# PAYL0012_GMSK_Prototyping_Board_no_proto.net
KiCad netlist of a schematic drawn in Altium Designer
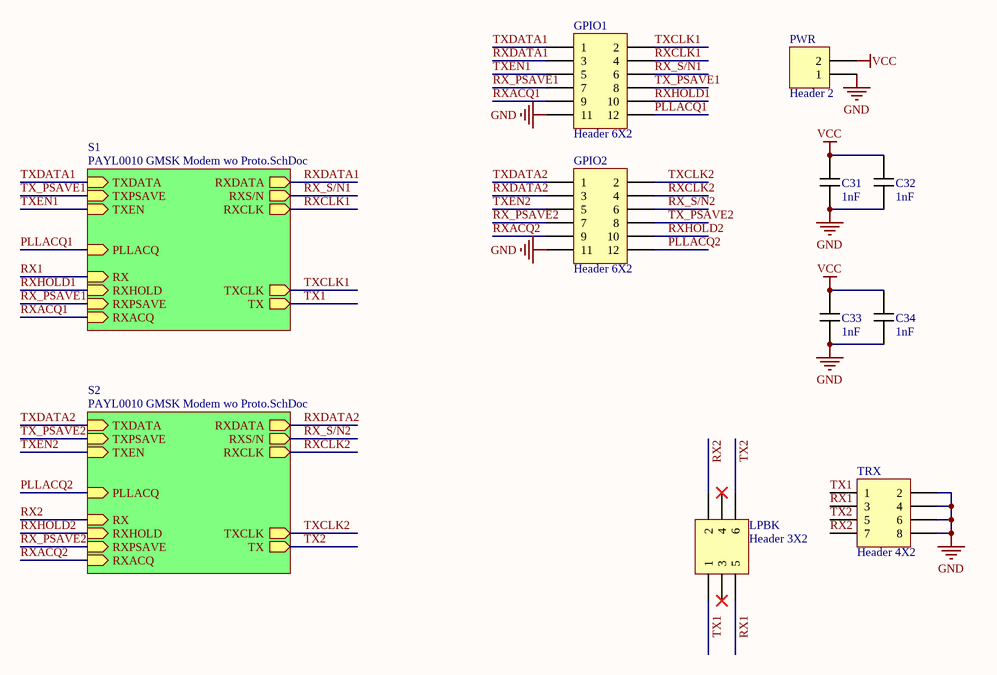
[diagram p0: PAYL0012 GMSK Prototyping Board no proto.SchDoc]

(export (version "E")
  (design (tool "Eeschema 10.0.6"))
  (components
    (comp (ref "C31")
      (value "1nF")
      (footprint "0805 Cap")
      (description "0805 MLCC - X7R, 10%")
      (fields (field (name "Comment") "0805 Cap"))
      (libsource (lib "GMSK Prototyping Board") (part "0805 MLCC - X7R, 10%"))
    )
    (comp (ref "C32")
      (value "1nF")
      (footprint "0805 Cap")
      (description "0805 MLCC - X7R, 10%")
      (fields (field (name "Comment") "0805 Cap"))
      (libsource (lib "GMSK Prototyping Board") (part "0805 MLCC - X7R, 10%"))
    )
    (comp (ref "C33")
      (value "1nF")
      (footprint "0805 Cap")
      (description "0805 MLCC - X7R, 10%")
      (fields (field (name "Comment") "0805 Cap"))
      (libsource (lib "GMSK Prototyping Board") (part "0805 MLCC - X7R, 10%"))
    )
    (comp (ref "C34")
      (value "1nF")
      (footprint "0805 Cap")
      (description "0805 MLCC - X7R, 10%")
      (fields (field (name "Comment") "0805 Cap"))
      (libsource (lib "GMSK Prototyping Board") (part "0805 MLCC - X7R, 10%"))
    )
    (comp (ref "GPIO1")
      (value "Header 6X2")
      (footprint "HDR2X6")
      (description "Header, 6-Pin, Dual row")
      (fields (field (name "PUBLISHER") "Altium Limited"))
      (libsource (lib "GMSK Prototyping Board") (part "Header 6X2"))
    )
    (comp (ref "GPIO2")
      (value "Header 6X2")
      (footprint "HDR2X6")
      (description "Header, 6-Pin, Dual row")
      (fields (field (name "PUBLISHER") "Altium Limited"))
      (libsource (lib "GMSK Prototyping Board") (part "Header 6X2"))
    )
    (comp (ref "LPBK")
      (value "Header 3X2")
      (footprint "HDR2X3")
      (description "Header, 3-Pin, Dual row")
      (fields (field (name "PUBLISHER") "Altium Limited"))
      (libsource (lib "GMSK Prototyping Board") (part "Header 3X2"))
    )
    (comp (ref "PWR")
      (value "Header 2")
      (footprint "HDR1X2")
      (description "Header, 2-Pin")
      (fields (field (name "PUBLISHER") "Altium Limited"))
      (libsource (lib "GMSK Prototyping Board") (part "Header 2"))
    )
    (comp (ref "TRX")
      (value "Header 4X2")
      (footprint "HDR2X4")
      (description "Header, 4-Pin, Dual row")
      (fields (field (name "PUBLISHER") "Altium Limited"))
      (libsource (lib "GMSK Prototyping Board") (part "Header 4X2"))
    )
  )
  (nets
    (net (code "1") (name "/PLLACQ1") (class "Default")
      (node (ref "GPIO1") (pin "12") (pinfunction "12_12") (pintype "passive"))
    )
    (net (code "2") (name "/PLLACQ2") (class "Default")
      (node (ref "GPIO2") (pin "12") (pinfunction "12_12") (pintype "passive"))
    )
    (net (code "3") (name "/RX1") (class "Default")
      (node (ref "LPBK") (pin "5") (pinfunction "5_5") (pintype "passive"))
      (node (ref "TRX") (pin "3") (pinfunction "3_3") (pintype "passive"))
    )
    (net (code "4") (name "/RX2") (class "Default")
      (node (ref "LPBK") (pin "2") (pinfunction "2_2") (pintype "passive"))
      (node (ref "TRX") (pin "7") (pinfunction "7_7") (pintype "passive"))
    )
    (net (code "5") (name "/RXACQ1") (class "Default")
      (node (ref "GPIO1") (pin "9") (pinfunction "9_9") (pintype "passive"))
    )
    (net (code "6") (name "/RXACQ2") (class "Default")
      (node (ref "GPIO2") (pin "9") (pinfunction "9_9") (pintype "passive"))
    )
    (net (code "7") (name "/RXCLK1") (class "Default")
      (node (ref "GPIO1") (pin "4") (pinfunction "4_4") (pintype "passive"))
    )
    (net (code "8") (name "/RXCLK2") (class "Default")
      (node (ref "GPIO2") (pin "4") (pinfunction "4_4") (pintype "passive"))
    )
    (net (code "9") (name "/RXDATA1") (class "Default")
      (node (ref "GPIO1") (pin "3") (pinfunction "3_3") (pintype "passive"))
    )
    (net (code "10") (name "/RXDATA2") (class "Default")
      (node (ref "GPIO2") (pin "3") (pinfunction "3_3") (pintype "passive"))
    )
    (net (code "11") (name "/RXHOLD1") (class "Default")
      (node (ref "GPIO1") (pin "10") (pinfunction "10_10") (pintype "passive"))
    )
    (net (code "12") (name "/RXHOLD2") (class "Default")
      (node (ref "GPIO2") (pin "10") (pinfunction "10_10") (pintype "passive"))
    )
    (net (code "13") (name "/RX_PSAVE1") (class "Default")
      (node (ref "GPIO1") (pin "7") (pinfunction "7_7") (pintype "passive"))
    )
    (net (code "14") (name "/RX_PSAVE2") (class "Default")
      (node (ref "GPIO2") (pin "7") (pinfunction "7_7") (pintype "passive"))
    )
    (net (code "15") (name "/RX_S{slash}N1") (class "Default")
      (node (ref "GPIO1") (pin "6") (pinfunction "6_6") (pintype "passive"))
    )
    (net (code "16") (name "/RX_S{slash}N2") (class "Default")
      (node (ref "GPIO2") (pin "6") (pinfunction "6_6") (pintype "passive"))
    )
    (net (code "17") (name "/TX1") (class "Default")
      (node (ref "LPBK") (pin "1") (pinfunction "1_1") (pintype "passive"))
      (node (ref "TRX") (pin "1") (pinfunction "1_1") (pintype "passive"))
    )
    (net (code "18") (name "/TX2") (class "Default")
      (node (ref "LPBK") (pin "6") (pinfunction "6_6") (pintype "passive"))
      (node (ref "TRX") (pin "5") (pinfunction "5_5") (pintype "passive"))
    )
    (net (code "19") (name "/TXCLK1") (class "Default")
      (node (ref "GPIO1") (pin "2") (pinfunction "2_2") (pintype "passive"))
    )
    (net (code "20") (name "/TXCLK2") (class "Default")
      (node (ref "GPIO2") (pin "2") (pinfunction "2_2") (pintype "passive"))
    )
    (net (code "21") (name "/TXDATA1") (class "Default")
      (node (ref "GPIO1") (pin "1") (pinfunction "1_1") (pintype "passive"))
    )
    (net (code "22") (name "/TXDATA2") (class "Default")
      (node (ref "GPIO2") (pin "1") (pinfunction "1_1") (pintype "passive"))
    )
    (net (code "23") (name "/TXEN1") (class "Default")
      (node (ref "GPIO1") (pin "5") (pinfunction "5_5") (pintype "passive"))
    )
    (net (code "24") (name "/TXEN2") (class "Default")
      (node (ref "GPIO2") (pin "5") (pinfunction "5_5") (pintype "passive"))
    )
    (net (code "25") (name "/TX_PSAVE1") (class "Default")
      (node (ref "GPIO1") (pin "8") (pinfunction "8_8") (pintype "passive"))
    )
    (net (code "26") (name "/TX_PSAVE2") (class "Default")
      (node (ref "GPIO2") (pin "8") (pinfunction "8_8") (pintype "passive"))
    )
    (net (code "27") (name "GND") (class "Default")
      (node (ref "C31") (pin "2") (pinfunction "2_2") (pintype "passive"))
      (node (ref "C32") (pin "2") (pinfunction "2_2") (pintype "passive"))
      (node (ref "C33") (pin "1") (pinfunction "1_1") (pintype "passive"))
      (node (ref "C34") (pin "1") (pinfunction "1_1") (pintype "passive"))
      (node (ref "GPIO1") (pin "11") (pinfunction "11_11") (pintype "passive"))
      (node (ref "GPIO2") (pin "11") (pinfunction "11_11") (pintype "passive"))
      (node (ref "PWR") (pin "1") (pinfunction "1_1") (pintype "passive"))
      (node (ref "TRX") (pin "2") (pinfunction "2_2") (pintype "passive"))
      (node (ref "TRX") (pin "4") (pinfunction "4_4") (pintype "passive"))
      (node (ref "TRX") (pin "6") (pinfunction "6_6") (pintype "passive"))
      (node (ref "TRX") (pin "8") (pinfunction "8_8") (pintype "passive"))
    )
    (net (code "28") (name "VCC") (class "Default")
      (node (ref "C31") (pin "1") (pinfunction "1_1") (pintype "passive"))
      (node (ref "C32") (pin "1") (pinfunction "1_1") (pintype "passive"))
      (node (ref "C33") (pin "2") (pinfunction "2_2") (pintype "passive"))
      (node (ref "C34") (pin "2") (pinfunction "2_2") (pintype "passive"))
      (node (ref "PWR") (pin "2") (pinfunction "2_2") (pintype "passive"))
    )
    (net (code "29") (name "unconnected-(LPBK-Pad3)") (class "Default")
      (node (ref "LPBK") (pin "3") (pinfunction "3_3") (pintype "passive+no_connect"))
    )
    (net (code "30") (name "unconnected-(LPBK-Pad4)") (class "Default")
      (node (ref "LPBK") (pin "4") (pinfunction "4_4") (pintype "passive+no_connect"))
    )
  )
)
